# Sample_End_Effector.net
KiCad netlist of a schematic drawn in EAGLE
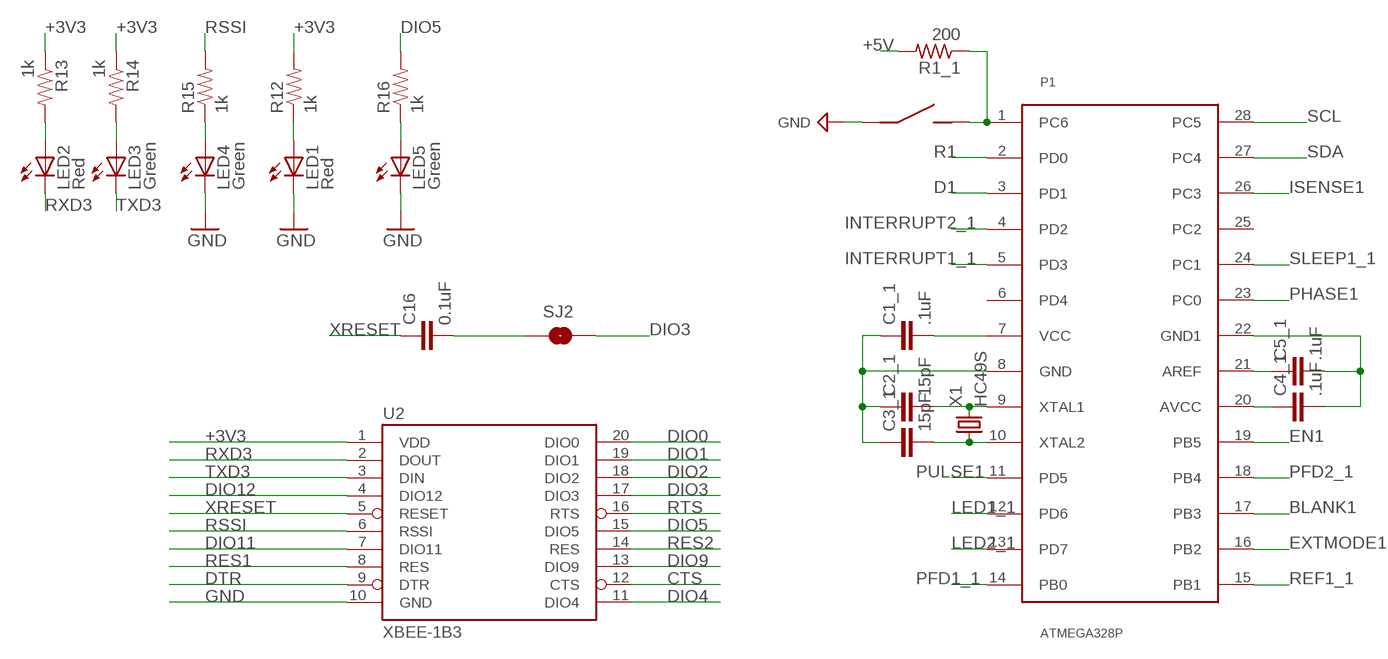
[diagram p0: schematic, sheet 1]
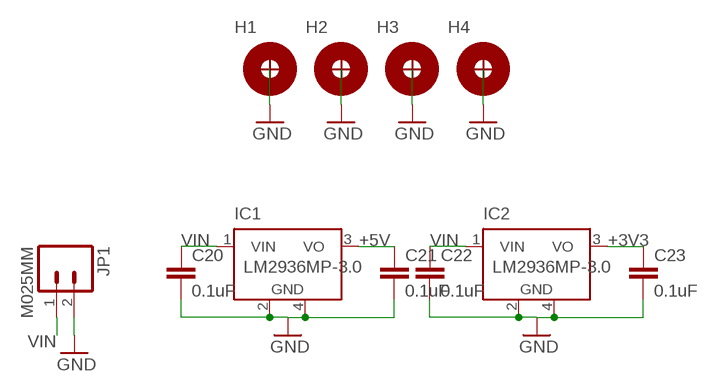
[diagram p1: schematic, sheet 2]

(export (version "E")
  (design (tool "Eeschema 10.0.6"))
  (components
    (comp (ref "C1_1")
      (value ".1uF")
      (footprint "eagle-import:C_0805")
      (libsource (lib "eagle-import") (part "C_CAP_0805"))
    )
    (comp (ref "C2_1")
      (value "15pF")
      (footprint "eagle-import:C_0805")
      (libsource (lib "eagle-import") (part "C_CAP_0805"))
    )
    (comp (ref "C3_1")
      (value "15pF")
      (footprint "eagle-import:C_0805")
      (libsource (lib "eagle-import") (part "C_CAP_0805"))
    )
    (comp (ref "C4_1")
      (value ".1uF")
      (footprint "eagle-import:C_0805")
      (libsource (lib "eagle-import") (part "C_CAP_0805"))
    )
    (comp (ref "C5_1")
      (value ".1uF")
      (footprint "eagle-import:C_0805")
      (libsource (lib "eagle-import") (part "C_CAP_0805"))
    )
    (comp (ref "C16")
      (value "0.1uF")
      (footprint "eagle-import:0603-CAP")
      (libsource (lib "eagle-import") (part "0.1UF-25V(+80/-20%)(0603)"))
    )
    (comp (ref "LED1")
      (value "Red")
      (footprint "eagle-import:LED-0603")
      (libsource (lib "eagle-import") (part "LED-RED0603"))
    )
    (comp (ref "LED2")
      (value "Red")
      (footprint "eagle-import:LED-0603")
      (libsource (lib "eagle-import") (part "LED-RED0603"))
    )
    (comp (ref "LED3")
      (value "Green")
      (footprint "eagle-import:LED-0603")
      (libsource (lib "eagle-import") (part "LED-GREEN0603"))
    )
    (comp (ref "LED4")
      (value "Green")
      (footprint "eagle-import:LED-0603")
      (libsource (lib "eagle-import") (part "LED-GREEN0603"))
    )
    (comp (ref "LED5")
      (value "Green")
      (footprint "eagle-import:LED-0603")
      (libsource (lib "eagle-import") (part "LED-GREEN0603"))
    )
    (comp (ref "P1")
      (value "ATMEGA328P")
      (footprint "eagle-import:DIP28")
      (libsource (lib "eagle-import") (part "Q_ATMEGA328P"))
    )
    (comp (ref "R1_1")
      (value "200")
      (footprint "eagle-import:R_0805")
      (libsource (lib "eagle-import") (part "R_RES_0805"))
    )
    (comp (ref "R12")
      (value "1k")
      (footprint "eagle-import:0603-RES")
      (libsource (lib "eagle-import") (part "1KOHM1/10W1%(0603)"))
    )
    (comp (ref "R13")
      (value "1k")
      (footprint "eagle-import:0603-RES")
      (libsource (lib "eagle-import") (part "1KOHM1/10W1%(0603)"))
    )
    (comp (ref "R14")
      (value "1k")
      (footprint "eagle-import:0603-RES")
      (libsource (lib "eagle-import") (part "1KOHM1/10W1%(0603)"))
    )
    (comp (ref "R15")
      (value "1k")
      (footprint "eagle-import:0603-RES")
      (libsource (lib "eagle-import") (part "1KOHM1/10W1%(0603)"))
    )
    (comp (ref "R16")
      (value "1k")
      (footprint "eagle-import:0603-RES")
      (libsource (lib "eagle-import") (part "1KOHM1/10W1%(0603)"))
    )
    (comp (ref "S1")
      (value "J_MC32857")
      (footprint "eagle-import:J_TOGGLE")
      (libsource (lib "eagle-import") (part "J_MC32857"))
    )
    (comp (ref "SJ2")
      (value "SOLDERJUMPERTRACE")
      (footprint "eagle-import:SJ_2S-TRACE")
      (libsource (lib "eagle-import") (part "SOLDERJUMPERTRACE"))
    )
    (comp (ref "U2")
      (value "XBEE-1B3")
      (footprint "eagle-import:XBEE-SMD")
      (libsource (lib "eagle-import") (part "XBEE-1B3"))
    )
    (comp (ref "X1")
      (value "HC49S")
      (footprint "eagle-import:HC-49")
      (libsource (lib "eagle-import") (part "X_HC49SCRYSTAL"))
    )
    (comp (ref "C20")
      (value "0.1uF")
      (footprint "eagle-import:0603-CAP")
      (libsource (lib "eagle-import") (part "0.1UF-25V(+80/-20%)(0603)"))
    )
    (comp (ref "C21")
      (value "0.1uF")
      (footprint "eagle-import:0603-CAP")
      (libsource (lib "eagle-import") (part "0.1UF-25V(+80/-20%)(0603)"))
    )
    (comp (ref "C22")
      (value "0.1uF")
      (footprint "eagle-import:0603-CAP")
      (libsource (lib "eagle-import") (part "0.1UF-25V(+80/-20%)(0603)"))
    )
    (comp (ref "C23")
      (value "0.1uF")
      (footprint "eagle-import:0603-CAP")
      (libsource (lib "eagle-import") (part "0.1UF-25V(+80/-20%)(0603)"))
    )
    (comp (ref "H1")
      (value "H_MNTHOLE_#4")
      (footprint "eagle-import:H_MNTHOLE_#4")
      (libsource (lib "eagle-import") (part "H_MNTHOLE_#4"))
    )
    (comp (ref "H2")
      (value "H_MNTHOLE_#4")
      (footprint "eagle-import:H_MNTHOLE_#4")
      (libsource (lib "eagle-import") (part "H_MNTHOLE_#4"))
    )
    (comp (ref "H3")
      (value "H_MNTHOLE_#4")
      (footprint "eagle-import:H_MNTHOLE_#4")
      (libsource (lib "eagle-import") (part "H_MNTHOLE_#4"))
    )
    (comp (ref "H4")
      (value "H_MNTHOLE_#4")
      (footprint "eagle-import:H_MNTHOLE_#4")
      (libsource (lib "eagle-import") (part "H_MNTHOLE_#4"))
    )
    (comp (ref "IC1")
      (value "LM2936MP-3.0")
      (footprint "eagle-import:SOT223")
      (fields (field (name "MF") "NATIONAL SEMICONDUCTOR") (field (name "MPN") "LM2936MP-3.0/NOPB"))
      (libsource (lib "eagle-import") (part "LM2936MP?-3.0"))
    )
    (comp (ref "IC2")
      (value "LM2936MP-3.0")
      (footprint "eagle-import:SOT223")
      (fields (field (name "MF") "NATIONAL SEMICONDUCTOR") (field (name "MPN") "LM2936MP-3.0/NOPB"))
      (libsource (lib "eagle-import") (part "LM2936MP?-3.0"))
    )
    (comp (ref "JP1")
      (value "M025MM")
      (footprint "eagle-import:SCREWTERMINAL-5MM-2")
      (libsource (lib "eagle-import") (part "M025MM"))
    )
  )
  (nets
    (net (code "1") (name "+3V3") (class "Default")
      (node (ref "C23") (pin "1") (pinfunction "1_1") (pintype "passive"))
      (node (ref "IC2") (pin "3") (pinfunction "VO_3") (pintype "passive"))
      (node (ref "R12") (pin "2") (pinfunction "2_2") (pintype "passive"))
      (node (ref "R13") (pin "1") (pinfunction "1_1") (pintype "passive"))
      (node (ref "R14") (pin "1") (pinfunction "1_1") (pintype "passive"))
      (node (ref "U2") (pin "1") (pinfunction "VDD_1") (pintype "power_in"))
    )
    (net (code "2") (name "+5V") (class "Default")
      (node (ref "C1_1") (pin "2") (pinfunction "2_2") (pintype "passive"))
      (node (ref "C21") (pin "1") (pinfunction "1_1") (pintype "passive"))
      (node (ref "C4_1") (pin "1") (pinfunction "1_1") (pintype "passive"))
      (node (ref "IC1") (pin "3") (pinfunction "VO_3") (pintype "passive"))
      (node (ref "P1") (pin "20") (pinfunction "AVCC_20") (pintype "bidirectional"))
      (node (ref "P1") (pin "7") (pinfunction "VCC_7") (pintype "bidirectional"))
      (node (ref "R1_1") (pin "2") (pinfunction "2_2") (pintype "passive"))
    )
    (net (code "3") (name "BLANK1") (class "Default")
      (node (ref "P1") (pin "17") (pinfunction "PB3_17") (pintype "bidirectional"))
    )
    (net (code "4") (name "CTS") (class "Default")
      (node (ref "U2") (pin "12") (pinfunction "CTS_12") (pintype "output"))
    )
    (net (code "5") (name "D1") (class "Default")
      (node (ref "P1") (pin "3") (pinfunction "PD1_3") (pintype "bidirectional"))
    )
    (net (code "6") (name "DIO0") (class "Default")
      (node (ref "U2") (pin "20") (pinfunction "DIO0_20") (pintype "bidirectional"))
    )
    (net (code "7") (name "DIO1") (class "Default")
      (node (ref "U2") (pin "19") (pinfunction "DIO1_19") (pintype "bidirectional"))
    )
    (net (code "8") (name "DIO2") (class "Default")
      (node (ref "U2") (pin "18") (pinfunction "DIO2_18") (pintype "bidirectional"))
    )
    (net (code "9") (name "DIO3") (class "Default")
      (node (ref "SJ2") (pin "2") (pinfunction "2_2") (pintype "passive"))
      (node (ref "U2") (pin "17") (pinfunction "DIO3_17") (pintype "bidirectional"))
    )
    (net (code "10") (name "DIO4") (class "Default")
      (node (ref "U2") (pin "11") (pinfunction "DIO4_11") (pintype "bidirectional"))
    )
    (net (code "11") (name "DIO5") (class "Default")
      (node (ref "R16") (pin "2") (pinfunction "2_2") (pintype "passive"))
      (node (ref "U2") (pin "15") (pinfunction "DIO5_15") (pintype "bidirectional"))
    )
    (net (code "12") (name "DIO9") (class "Default")
      (node (ref "U2") (pin "13") (pinfunction "DIO9_13") (pintype "bidirectional"))
    )
    (net (code "13") (name "DIO11") (class "Default")
      (node (ref "U2") (pin "7") (pinfunction "DIO11_7") (pintype "bidirectional"))
    )
    (net (code "14") (name "DIO12") (class "Default")
      (node (ref "U2") (pin "4") (pinfunction "DIO12_4") (pintype "bidirectional"))
    )
    (net (code "15") (name "DTR") (class "Default")
      (node (ref "U2") (pin "9") (pinfunction "DTR_9") (pintype "bidirectional"))
    )
    (net (code "16") (name "EN1") (class "Default")
      (node (ref "P1") (pin "19") (pinfunction "PB5_19") (pintype "bidirectional"))
    )
    (net (code "17") (name "EXTMODE1") (class "Default")
      (node (ref "P1") (pin "16") (pinfunction "PB2_16") (pintype "bidirectional"))
    )
    (net (code "18") (name "GND") (class "Default")
      (node (ref "C1_1") (pin "1") (pinfunction "1_1") (pintype "passive"))
      (node (ref "C20") (pin "2") (pinfunction "2_2") (pintype "passive"))
      (node (ref "C21") (pin "2") (pinfunction "2_2") (pintype "passive"))
      (node (ref "C22") (pin "2") (pinfunction "2_2") (pintype "passive"))
      (node (ref "C23") (pin "2") (pinfunction "2_2") (pintype "passive"))
      (node (ref "C2_1") (pin "1") (pinfunction "1_1") (pintype "passive"))
      (node (ref "C3_1") (pin "1") (pinfunction "1_1") (pintype "passive"))
      (node (ref "C4_1") (pin "2") (pinfunction "2_2") (pintype "passive"))
      (node (ref "C5_1") (pin "2") (pinfunction "2_2") (pintype "passive"))
      (node (ref "H1") (pin "1") (pinfunction "1_1") (pintype "passive"))
      (node (ref "H2") (pin "1") (pinfunction "1_1") (pintype "passive"))
      (node (ref "H3") (pin "1") (pinfunction "1_1") (pintype "passive"))
      (node (ref "H4") (pin "1") (pinfunction "1_1") (pintype "passive"))
      (node (ref "IC1") (pin "2") (pinfunction "GND_2") (pintype "passive"))
      (node (ref "IC1") (pin "4") (pinfunction "GND_4") (pintype "passive"))
      (node (ref "IC2") (pin "2") (pinfunction "GND_2") (pintype "passive"))
      (node (ref "IC2") (pin "4") (pinfunction "GND_4") (pintype "passive"))
      (node (ref "JP1") (pin "2") (pinfunction "2_2") (pintype "passive"))
      (node (ref "LED1") (pin "C") (pinfunction "C_C") (pintype "passive"))
      (node (ref "LED4") (pin "C") (pinfunction "C_C") (pintype "passive"))
      (node (ref "LED5") (pin "C") (pinfunction "C_C") (pintype "passive"))
      (node (ref "P1") (pin "22") (pinfunction "GND1_22") (pintype "bidirectional"))
      (node (ref "P1") (pin "8") (pinfunction "GND_8") (pintype "bidirectional"))
      (node (ref "S1") (pin "P$1") (pinfunction "1_P$1") (pintype "bidirectional"))
      (node (ref "U2") (pin "10") (pinfunction "GND_10") (pintype "power_in"))
    )
    (net (code "19") (name "INTERRUPT1_1") (class "Default")
      (node (ref "P1") (pin "5") (pinfunction "PD3_5") (pintype "bidirectional"))
    )
    (net (code "20") (name "INTERRUPT2_1") (class "Default")
      (node (ref "P1") (pin "4") (pinfunction "PD2_4") (pintype "bidirectional"))
    )
    (net (code "21") (name "ISENSE1") (class "Default")
      (node (ref "P1") (pin "26") (pinfunction "PC3_26") (pintype "bidirectional"))
    )
    (net (code "22") (name "LED1_1") (class "Default")
      (node (ref "P1") (pin "12") (pinfunction "PD6_12") (pintype "bidirectional"))
    )
    (net (code "23") (name "LED2_1") (class "Default")
      (node (ref "P1") (pin "13") (pinfunction "PD7_13") (pintype "bidirectional"))
    )
    (net (code "24") (name "Net-(C16-Pad2)") (class "Default")
      (node (ref "C16") (pin "2") (pinfunction "2_2") (pintype "passive"))
      (node (ref "SJ2") (pin "1") (pinfunction "1_1") (pintype "passive"))
    )
    (net (code "25") (name "Net-(LED1-PadA)") (class "Default")
      (node (ref "LED1") (pin "A") (pinfunction "A_A") (pintype "passive"))
      (node (ref "R12") (pin "1") (pinfunction "1_1") (pintype "passive"))
    )
    (net (code "26") (name "Net-(LED2-PadA)") (class "Default")
      (node (ref "LED2") (pin "A") (pinfunction "A_A") (pintype "passive"))
      (node (ref "R13") (pin "2") (pinfunction "2_2") (pintype "passive"))
    )
    (net (code "27") (name "Net-(LED3-PadA)") (class "Default")
      (node (ref "LED3") (pin "A") (pinfunction "A_A") (pintype "passive"))
      (node (ref "R14") (pin "2") (pinfunction "2_2") (pintype "passive"))
    )
    (net (code "28") (name "Net-(LED4-PadA)") (class "Default")
      (node (ref "LED4") (pin "A") (pinfunction "A_A") (pintype "passive"))
      (node (ref "R15") (pin "1") (pinfunction "1_1") (pintype "passive"))
    )
    (net (code "29") (name "Net-(LED5-PadA)") (class "Default")
      (node (ref "LED5") (pin "A") (pinfunction "A_A") (pintype "passive"))
      (node (ref "R16") (pin "1") (pinfunction "1_1") (pintype "passive"))
    )
    (net (code "30") (name "Net-(P1-AREF)") (class "Default")
      (node (ref "C5_1") (pin "1") (pinfunction "1_1") (pintype "passive"))
      (node (ref "P1") (pin "21") (pinfunction "AREF_21") (pintype "bidirectional"))
    )
    (net (code "31") (name "Net-(P1-PC6)") (class "Default")
      (node (ref "P1") (pin "1") (pinfunction "PC6_1") (pintype "bidirectional"))
      (node (ref "R1_1") (pin "1") (pinfunction "1_1") (pintype "passive"))
      (node (ref "S1") (pin "P$2") (pinfunction "2_P$2") (pintype "bidirectional"))
    )
    (net (code "32") (name "Net-(P1-XTAL1)") (class "Default")
      (node (ref "C2_1") (pin "2") (pinfunction "2_2") (pintype "passive"))
      (node (ref "P1") (pin "9") (pinfunction "XTAL1_9") (pintype "bidirectional"))
      (node (ref "X1") (pin "P$2") (pinfunction "2_P$2") (pintype "passive"))
    )
    (net (code "33") (name "Net-(P1-XTAL2)") (class "Default")
      (node (ref "C3_1") (pin "2") (pinfunction "2_2") (pintype "passive"))
      (node (ref "P1") (pin "10") (pinfunction "XTAL2_10") (pintype "bidirectional"))
      (node (ref "X1") (pin "P$1") (pinfunction "1_P$1") (pintype "passive"))
    )
    (net (code "34") (name "PFD1_1") (class "Default")
      (node (ref "P1") (pin "14") (pinfunction "PB0_14") (pintype "bidirectional"))
    )
    (net (code "35") (name "PFD2_1") (class "Default")
      (node (ref "P1") (pin "18") (pinfunction "PB4_18") (pintype "bidirectional"))
    )
    (net (code "36") (name "PHASE1") (class "Default")
      (node (ref "P1") (pin "23") (pinfunction "PC0_23") (pintype "bidirectional"))
    )
    (net (code "37") (name "PULSE1") (class "Default")
      (node (ref "P1") (pin "11") (pinfunction "PD5_11") (pintype "bidirectional"))
    )
    (net (code "38") (name "R1") (class "Default")
      (node (ref "P1") (pin "2") (pinfunction "PD0_2") (pintype "bidirectional"))
    )
    (net (code "39") (name "REF1_1") (class "Default")
      (node (ref "P1") (pin "15") (pinfunction "PB1_15") (pintype "bidirectional"))
    )
    (net (code "40") (name "RES1") (class "Default")
      (node (ref "U2") (pin "8") (pinfunction "RES_8") (pintype "bidirectional"))
    )
    (net (code "41") (name "RES2") (class "Default")
      (node (ref "U2") (pin "14") (pinfunction "RES_14") (pintype "bidirectional"))
    )
    (net (code "42") (name "RSSI") (class "Default")
      (node (ref "R15") (pin "2") (pinfunction "2_2") (pintype "passive"))
      (node (ref "U2") (pin "6") (pinfunction "RSSI_6") (pintype "bidirectional"))
    )
    (net (code "43") (name "RTS") (class "Default")
      (node (ref "U2") (pin "16") (pinfunction "RTS_16") (pintype "input"))
    )
    (net (code "44") (name "RXD3") (class "Default")
      (node (ref "LED2") (pin "C") (pinfunction "C_C") (pintype "passive"))
      (node (ref "U2") (pin "2") (pinfunction "DOUT_2") (pintype "output"))
    )
    (net (code "45") (name "SCL") (class "Default")
      (node (ref "P1") (pin "28") (pinfunction "PC5_28") (pintype "bidirectional"))
    )
    (net (code "46") (name "SDA") (class "Default")
      (node (ref "P1") (pin "27") (pinfunction "PC4_27") (pintype "bidirectional"))
    )
    (net (code "47") (name "SLEEP1_1") (class "Default")
      (node (ref "P1") (pin "24") (pinfunction "PC1_24") (pintype "bidirectional"))
    )
    (net (code "48") (name "TXD3") (class "Default")
      (node (ref "LED3") (pin "C") (pinfunction "C_C") (pintype "passive"))
      (node (ref "U2") (pin "3") (pinfunction "DIN_3") (pintype "input"))
    )
    (net (code "49") (name "VIN") (class "Default")
      (node (ref "C20") (pin "1") (pinfunction "1_1") (pintype "passive"))
      (node (ref "C22") (pin "1") (pinfunction "1_1") (pintype "passive"))
      (node (ref "IC1") (pin "1") (pinfunction "VIN_1") (pintype "input"))
      (node (ref "IC2") (pin "1") (pinfunction "VIN_1") (pintype "input"))
      (node (ref "JP1") (pin "1") (pinfunction "1_1") (pintype "passive"))
    )
    (net (code "50") (name "XRESET") (class "Default")
      (node (ref "C16") (pin "1") (pinfunction "1_1") (pintype "passive"))
      (node (ref "U2") (pin "5") (pinfunction "RESET_5") (pintype "input"))
    )
    (net (code "51") (name "unconnected-(P1-PC2-Pad25)") (class "Default")
      (node (ref "P1") (pin "25") (pinfunction "PC2_25") (pintype "bidirectional"))
    )
    (net (code "52") (name "unconnected-(P1-PD4-Pad6)") (class "Default")
      (node (ref "P1") (pin "6") (pinfunction "PD4_6") (pintype "bidirectional"))
    )
  )
)
